# Schematic_start_module_sumo_IR_V0_17.net
KiCad netlist of a schematic drawn in EAGLE
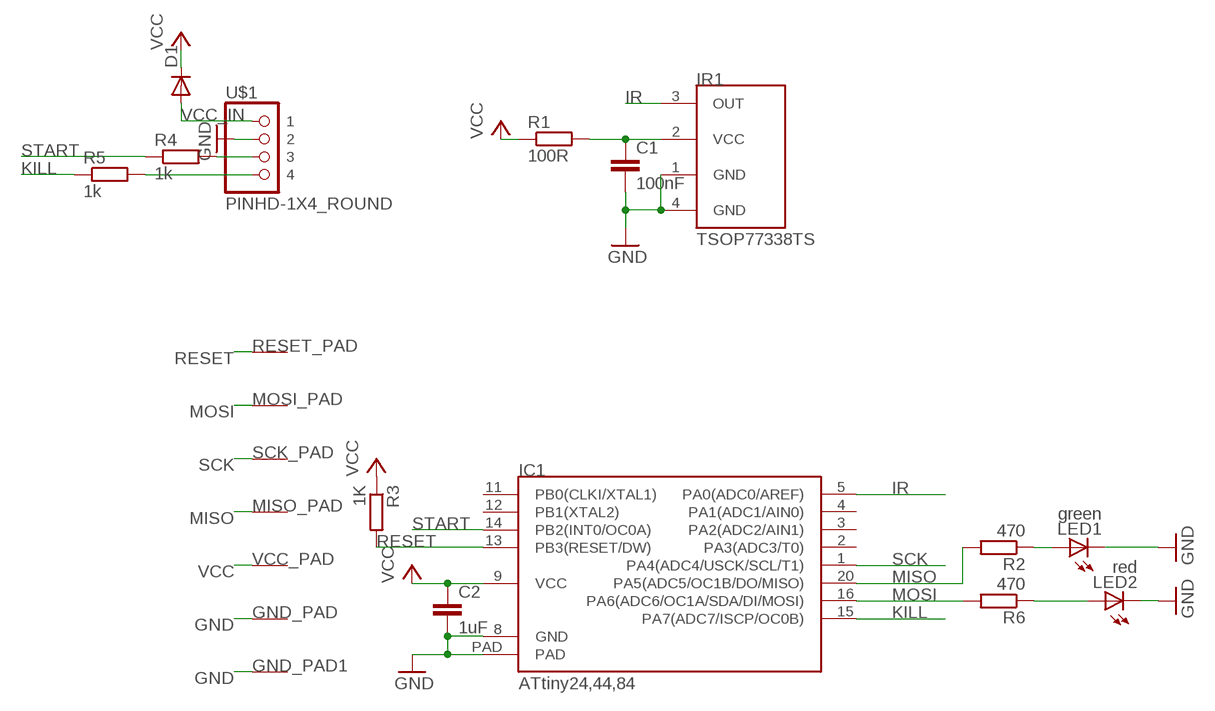
[diagram p0: schematic, sheet 1]

(export (version "E")
  (design (tool "Eeschema 10.0.6"))
  (components
    (comp (ref "C1")
      (value "100nF")
      (footprint "eagle-import:C0603")
      (libsource (lib "eagle-import") (part "C-EUC0603"))
    )
    (comp (ref "C2")
      (value "1uF")
      (footprint "eagle-import:C0603")
      (libsource (lib "eagle-import") (part "C-EUC0603"))
    )
    (comp (ref "D1")
      (value "DIODE-SOD523")
      (footprint "eagle-import:SOD523")
      (libsource (lib "eagle-import") (part "DIODE-SOD523"))
    )
    (comp (ref "GND_PAD")
      (value "PAD50X50")
      (footprint "eagle-import:PAD_50X50")
      (libsource (lib "eagle-import") (part "PAD50X50"))
    )
    (comp (ref "GND_PAD1")
      (value "PAD75X75")
      (footprint "eagle-import:PAD_75X75")
      (libsource (lib "eagle-import") (part "PAD75X75"))
    )
    (comp (ref "IC1")
      (value "ATTINY24,44,84_QFNVQFN")
      (footprint "eagle-import:VQFN20")
      (libsource (lib "eagle-import") (part "ATTINY24,44,84_QFNVQFN"))
    )
    (comp (ref "IR1")
      (value "TSOP77338TS")
      (footprint "eagle-import:TSOP77338")
      (libsource (lib "eagle-import") (part "TSOP77338TS"))
    )
    (comp (ref "LED1")
      (value "green")
      (footprint "eagle-import:0603_SMALL")
      (libsource (lib "eagle-import") (part "LED0603"))
    )
    (comp (ref "LED2")
      (value "red")
      (footprint "eagle-import:0603_SMALL")
      (libsource (lib "eagle-import") (part "LED0603"))
    )
    (comp (ref "MISO_PAD")
      (value "PAD50X50")
      (footprint "eagle-import:PAD_50X50")
      (libsource (lib "eagle-import") (part "PAD50X50"))
    )
    (comp (ref "MOSI_PAD")
      (value "PAD50X50")
      (footprint "eagle-import:PAD_50X50")
      (libsource (lib "eagle-import") (part "PAD50X50"))
    )
    (comp (ref "R1")
      (value "100R")
      (footprint "eagle-import:R0402")
      (libsource (lib "eagle-import") (part "R-EU_R0402"))
    )
    (comp (ref "R2")
      (value "470")
      (footprint "eagle-import:R0402")
      (libsource (lib "eagle-import") (part "R-EU_R0402"))
    )
    (comp (ref "R3")
      (value "1K")
      (footprint "eagle-import:R0402")
      (libsource (lib "eagle-import") (part "R-EU_R0402"))
    )
    (comp (ref "R4")
      (value "1k")
      (footprint "eagle-import:R0402")
      (libsource (lib "eagle-import") (part "R-EU_R0402"))
    )
    (comp (ref "R5")
      (value "1k")
      (footprint "eagle-import:R0402")
      (libsource (lib "eagle-import") (part "R-EU_R0402"))
    )
    (comp (ref "R6")
      (value "470")
      (footprint "eagle-import:R0402")
      (libsource (lib "eagle-import") (part "R-EU_R0402"))
    )
    (comp (ref "RESET_PAD")
      (value "PAD50X50")
      (footprint "eagle-import:PAD_50X50")
      (libsource (lib "eagle-import") (part "PAD50X50"))
    )
    (comp (ref "SCK_PAD")
      (value "mosi")
      (footprint "eagle-import:PAD_75X75")
      (libsource (lib "eagle-import") (part "PAD75X75"))
    )
    (comp (ref "U$1")
      (value "PINHD-1X4_ROUND")
      (footprint "eagle-import:1X04_ROUND")
      (libsource (lib "eagle-import") (part "PINHD-1X4_ROUND"))
    )
    (comp (ref "VCC_PAD")
      (value "PAD50X50")
      (footprint "eagle-import:PAD_50X50")
      (libsource (lib "eagle-import") (part "PAD50X50"))
    )
  )
  (nets
    (net (code "1") (name "/IR") (class "Default")
      (node (ref "IC1") (pin "5") (pinfunction "PA0(ADC0/AREF)_5") (pintype "bidirectional"))
      (node (ref "IR1") (pin "3") (pinfunction "OUT_3") (pintype "bidirectional"))
    )
    (net (code "2") (name "/KILL") (class "Default")
      (node (ref "IC1") (pin "15") (pinfunction "PA7(ADC7/ISCP/OC0B)_15") (pintype "bidirectional"))
      (node (ref "R5") (pin "1") (pinfunction "1_1") (pintype "passive"))
    )
    (net (code "3") (name "/MISO") (class "Default")
      (node (ref "IC1") (pin "20") (pinfunction "PA5(ADC5/OC1B/DO/MISO)_20") (pintype "bidirectional"))
      (node (ref "MISO_PAD") (pin "P$1") (pinfunction "PAD_P$1") (pintype "power_in"))
      (node (ref "R2") (pin "2") (pinfunction "2_2") (pintype "passive"))
    )
    (net (code "4") (name "/MOSI") (class "Default")
      (node (ref "IC1") (pin "16") (pinfunction "PA6(ADC6/OC1A/SDA/DI/MOSI)_16") (pintype "bidirectional"))
      (node (ref "MOSI_PAD") (pin "P$1") (pinfunction "PAD_P$1") (pintype "power_in"))
      (node (ref "R6") (pin "2") (pinfunction "2_2") (pintype "passive"))
    )
    (net (code "5") (name "/RESET") (class "Default")
      (node (ref "IC1") (pin "13") (pinfunction "PB3(RESET/DW)_13") (pintype "bidirectional"))
      (node (ref "R3") (pin "2") (pinfunction "2_2") (pintype "passive"))
      (node (ref "RESET_PAD") (pin "P$1") (pinfunction "PAD_P$1") (pintype "power_in"))
    )
    (net (code "6") (name "/SCK") (class "Default")
      (node (ref "IC1") (pin "1") (pinfunction "PA4(ADC4/USCK/SCL/T1)_1") (pintype "bidirectional"))
      (node (ref "SCK_PAD") (pin "P$1") (pinfunction "PAD_P$1") (pintype "power_in"))
    )
    (net (code "7") (name "/START") (class "Default")
      (node (ref "IC1") (pin "14") (pinfunction "PB2(INT0/OC0A)_14") (pintype "bidirectional"))
      (node (ref "R4") (pin "1") (pinfunction "1_1") (pintype "passive"))
    )
    (net (code "8") (name "/VCC_IN") (class "Default")
      (node (ref "D1") (pin "A") (pinfunction "A_A") (pintype "passive"))
      (node (ref "U$1") (pin "1") (pinfunction "1_1") (pintype "passive"))
    )
    (net (code "9") (name "GND") (class "Default")
      (node (ref "C1") (pin "2") (pinfunction "2_2") (pintype "passive"))
      (node (ref "C2") (pin "2") (pinfunction "2_2") (pintype "passive"))
      (node (ref "GND_PAD") (pin "P$1") (pinfunction "PAD_P$1") (pintype "power_in"))
      (node (ref "GND_PAD1") (pin "P$1") (pinfunction "PAD_P$1") (pintype "power_in"))
      (node (ref "IC1") (pin "8") (pinfunction "GND_8") (pintype "bidirectional"))
      (node (ref "IC1") (pin "PAD") (pinfunction "PAD_PAD") (pintype "bidirectional"))
      (node (ref "IR1") (pin "1") (pinfunction "GND_1") (pintype "bidirectional"))
      (node (ref "IR1") (pin "4") (pinfunction "GND_4") (pintype "bidirectional"))
      (node (ref "LED1") (pin "2") (pinfunction "C_2") (pintype "passive"))
      (node (ref "LED2") (pin "2") (pinfunction "C_2") (pintype "passive"))
      (node (ref "U$1") (pin "2") (pinfunction "2_2") (pintype "passive"))
    )
    (net (code "10") (name "Net-(IR1-VCC)") (class "Default")
      (node (ref "C1") (pin "1") (pinfunction "1_1") (pintype "passive"))
      (node (ref "IR1") (pin "2") (pinfunction "VCC_2") (pintype "bidirectional"))
      (node (ref "R1") (pin "2") (pinfunction "2_2") (pintype "passive"))
    )
    (net (code "11") (name "Net-(LED1-A)") (class "Default")
      (node (ref "LED1") (pin "1") (pinfunction "A_1") (pintype "passive"))
      (node (ref "R2") (pin "1") (pinfunction "1_1") (pintype "passive"))
    )
    (net (code "12") (name "Net-(LED2-A)") (class "Default")
      (node (ref "LED2") (pin "1") (pinfunction "A_1") (pintype "passive"))
      (node (ref "R6") (pin "1") (pinfunction "1_1") (pintype "passive"))
    )
    (net (code "13") (name "Net-(R4-Pad2)") (class "Default")
      (node (ref "R4") (pin "2") (pinfunction "2_2") (pintype "passive"))
      (node (ref "U$1") (pin "3") (pinfunction "3_3") (pintype "passive"))
    )
    (net (code "14") (name "Net-(R5-Pad2)") (class "Default")
      (node (ref "R5") (pin "2") (pinfunction "2_2") (pintype "passive"))
      (node (ref "U$1") (pin "4") (pinfunction "4_4") (pintype "passive"))
    )
    (net (code "15") (name "VCC") (class "Default")
      (node (ref "C2") (pin "1") (pinfunction "1_1") (pintype "passive"))
      (node (ref "D1") (pin "C") (pinfunction "C_C") (pintype "passive"))
      (node (ref "IC1") (pin "9") (pinfunction "VCC_9") (pintype "bidirectional"))
      (node (ref "R1") (pin "1") (pinfunction "1_1") (pintype "passive"))
      (node (ref "R3") (pin "1") (pinfunction "1_1") (pintype "passive"))
      (node (ref "VCC_PAD") (pin "P$1") (pinfunction "PAD_P$1") (pintype "power_in"))
    )
    (net (code "16") (name "unconnected-(IC1-PA1(ADC1{slash}AIN0)-Pad4)") (class "Default")
      (node (ref "IC1") (pin "4") (pinfunction "PA1(ADC1/AIN0)_4") (pintype "bidirectional"))
    )
    (net (code "17") (name "unconnected-(IC1-PA2(ADC2{slash}AIN1)-Pad3)") (class "Default")
      (node (ref "IC1") (pin "3") (pinfunction "PA2(ADC2/AIN1)_3") (pintype "bidirectional"))
    )
    (net (code "18") (name "unconnected-(IC1-PA3(ADC3{slash}T0)-Pad2)") (class "Default")
      (node (ref "IC1") (pin "2") (pinfunction "PA3(ADC3/T0)_2") (pintype "bidirectional"))
    )
    (net (code "19") (name "unconnected-(IC1-PB0(CLKI{slash}XTAL1)-Pad11)") (class "Default")
      (node (ref "IC1") (pin "11") (pinfunction "PB0(CLKI/XTAL1)_11") (pintype "bidirectional"))
    )
    (net (code "20") (name "unconnected-(IC1-PB1(XTAL2)-Pad12)") (class "Default")
      (node (ref "IC1") (pin "12") (pinfunction "PB1(XTAL2)_12") (pintype "bidirectional"))
    )
  )
)
